# norbi_lm_usb.net
KiCad netlist of a schematic drawn in Altium Designer
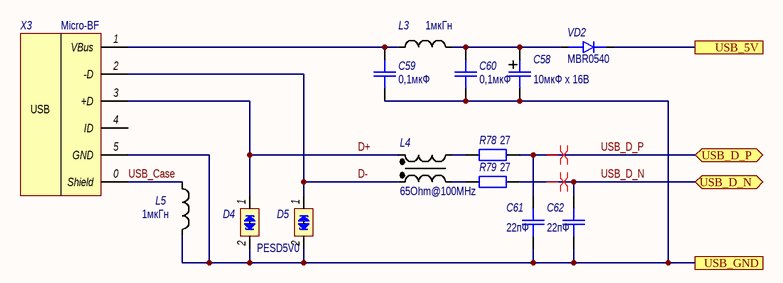
[diagram p0: norbi_lm_usb.SchDoc]

(export (version "E")
  (design (tool "Eeschema 10.0.6"))
  (components
    (comp (ref "C58")
      (value "10мкФ х 16В")
      (footprint "C_SMD_SIZE_B")
      (description "Поляризованный конеднсатор для поверхностного монтажа")
      (libsource (lib "my_passive") (part "C_pol_smd"))
    )
    (comp (ref "C59")
      (value "0,1мкФ")
      (footprint "CR-0603")
      (description "Конденсатор для поверхностного монтажа")
      (libsource (lib "my_passive") (part "C_smd"))
    )
    (comp (ref "C60")
      (value "0,1мкФ")
      (footprint "CR-0603")
      (description "Конденсатор для поверхностного монтажа")
      (libsource (lib "my_passive") (part "C_smd"))
    )
    (comp (ref "C61")
      (value "22пФ")
      (footprint "CR-0603")
      (description "Конденсатор для поверхностного монтажа")
      (libsource (lib "my_passive") (part "C_smd"))
    )
    (comp (ref "C62")
      (value "22пФ")
      (footprint "CR-0603")
      (description "Конденсатор для поверхностного монтажа")
      (libsource (lib "my_passive") (part "C_smd"))
    )
    (comp (ref "D4")
      (value "PESD5V0")
      (footprint "SOD-323")
      (description "Low capacitance bidirectional ESD protection diodes")
      (libsource (lib "my_semicond") (part "PESD5V0S"))
    )
    (comp (ref "D5")
      (value "PESD5V0")
      (footprint "SOD-323")
      (description "Low capacitance bidirectional ESD protection diodes")
      (libsource (lib "my_semicond") (part "PESD5V0S"))
    )
    (comp (ref "L3")
      (value "1мкГн")
      (footprint "CR-0805")
      (description "Индуктивность для поверхностнгого монтажа")
      (libsource (lib "my_passive") (part "L_smd"))
    )
    (comp (ref "L4")
      (value "65Ohm@100MHz")
      (footprint "ACM2012")
      (description "USB common mode filter")
      (libsource (lib "my_passive") (part "ACM2012_USB_CM_FILTER"))
    )
    (comp (ref "L5")
      (value "1мкГн")
      (footprint "CR-0805")
      (description "Индуктивность для поверхностнгого монтажа")
      (libsource (lib "my_passive") (part "L_smd"))
    )
    (comp (ref "R78")
      (value "27")
      (footprint "CR-0603")
      (description "Резистор для поверхностного монтажа")
      (libsource (lib "my_passive") (part "R_smd"))
    )
    (comp (ref "R79")
      (value "27")
      (footprint "CR-0603")
      (description "Резистор для поверхностного монтажа")
      (libsource (lib "my_passive") (part "R_smd"))
    )
    (comp (ref "VD2")
      (value "MBR0540")
      (footprint "SOD-323")
      (description "Schottky diode")
      (libsource (lib "my_semicond") (part "BAT60A"))
    )
    (comp (ref "X3")
      (value "mico-BF")
      (footprint "USB Micro-BF")
      (description "USB mico-BF")
      (fields (field (name "НАИМЕНОВАНИЕ") "Micro-BF"))
      (libsource (lib "my_connector") (part "MicroUSB"))
    )
  )
  (nets
    (net (code "1") (name "/D+") (class "Default")
      (node (ref "D4") (pin "1") (pinfunction "cathode_1_1") (pintype "power_in"))
      (node (ref "L4") (pin "2") (pinfunction "2_2") (pintype "passive"))
      (node (ref "X3") (pin "3") (pinfunction "+D_3") (pintype "passive"))
    )
    (net (code "2") (name "/D-") (class "Default")
      (node (ref "D5") (pin "1") (pinfunction "cathode_1_1") (pintype "power_in"))
      (node (ref "L4") (pin "1") (pinfunction "1_1") (pintype "passive"))
      (node (ref "X3") (pin "2") (pinfunction "-D_2") (pintype "passive"))
    )
    (net (code "3") (name "/USB_5V") (class "Default")
      (node (ref "VD2") (pin "1") (pinfunction "Cathode_1") (pintype "passive"))
    )
    (net (code "4") (name "/USB_Case") (class "Default")
      (node (ref "L5") (pin "1") (pinfunction "1_1") (pintype "passive"))
      (node (ref "X3") (pin "0") (pinfunction "Shield_0") (pintype "passive"))
    )
    (net (code "5") (name "/USB_D_N") (class "Default")
      (node (ref "C62") (pin "2") (pinfunction "2_2") (pintype "passive"))
      (node (ref "R79") (pin "1") (pinfunction "1_1") (pintype "passive"))
    )
    (net (code "6") (name "/USB_D_P") (class "Default")
      (node (ref "C61") (pin "2") (pinfunction "2_2") (pintype "passive"))
      (node (ref "R78") (pin "1") (pinfunction "1_1") (pintype "passive"))
    )
    (net (code "7") (name "/USB_GND") (class "Default")
      (node (ref "C58") (pin "2") (pinfunction "2_2") (pintype "passive"))
      (node (ref "C59") (pin "1") (pinfunction "1_1") (pintype "passive"))
      (node (ref "C60") (pin "1") (pinfunction "1_1") (pintype "passive"))
      (node (ref "C61") (pin "1") (pinfunction "1_1") (pintype "passive"))
      (node (ref "C62") (pin "1") (pinfunction "1_1") (pintype "passive"))
      (node (ref "D4") (pin "2") (pinfunction "cathode_2_2") (pintype "power_in"))
      (node (ref "D5") (pin "2") (pinfunction "cathode_2_2") (pintype "power_in"))
      (node (ref "L5") (pin "2") (pinfunction "2_2") (pintype "passive"))
      (node (ref "X3") (pin "5") (pinfunction "GND_5") (pintype "passive"))
    )
    (net (code "8") (name "Net-(L4-Pad3)") (class "Default")
      (node (ref "L4") (pin "3") (pinfunction "3_3") (pintype "passive"))
      (node (ref "R78") (pin "2") (pinfunction "2_2") (pintype "passive"))
    )
    (net (code "9") (name "Net-(L4-Pad4)") (class "Default")
      (node (ref "L4") (pin "4") (pinfunction "4_4") (pintype "passive"))
      (node (ref "R79") (pin "2") (pinfunction "2_2") (pintype "passive"))
    )
    (net (code "10") (name "Net-(VD2-Anode)") (class "Default")
      (node (ref "C58") (pin "1") (pinfunction "1_1") (pintype "passive"))
      (node (ref "C60") (pin "2") (pinfunction "2_2") (pintype "passive"))
      (node (ref "L3") (pin "2") (pinfunction "2_2") (pintype "passive"))
      (node (ref "VD2") (pin "2") (pinfunction "Anode_2") (pintype "passive"))
    )
    (net (code "11") (name "Net-(X3-VBus)") (class "Default")
      (node (ref "C59") (pin "2") (pinfunction "2_2") (pintype "passive"))
      (node (ref "L3") (pin "1") (pinfunction "1_1") (pintype "passive"))
      (node (ref "X3") (pin "1") (pinfunction "VBus_1") (pintype "passive"))
    )
    (net (code "12") (name "unconnected-(X3-ID-Pad4)") (class "Default")
      (node (ref "X3") (pin "4") (pinfunction "ID_4") (pintype "passive"))
    )
  )
)
